# AuxPowerSupply.net
KiCad netlist of a schematic drawn in Altium Designer
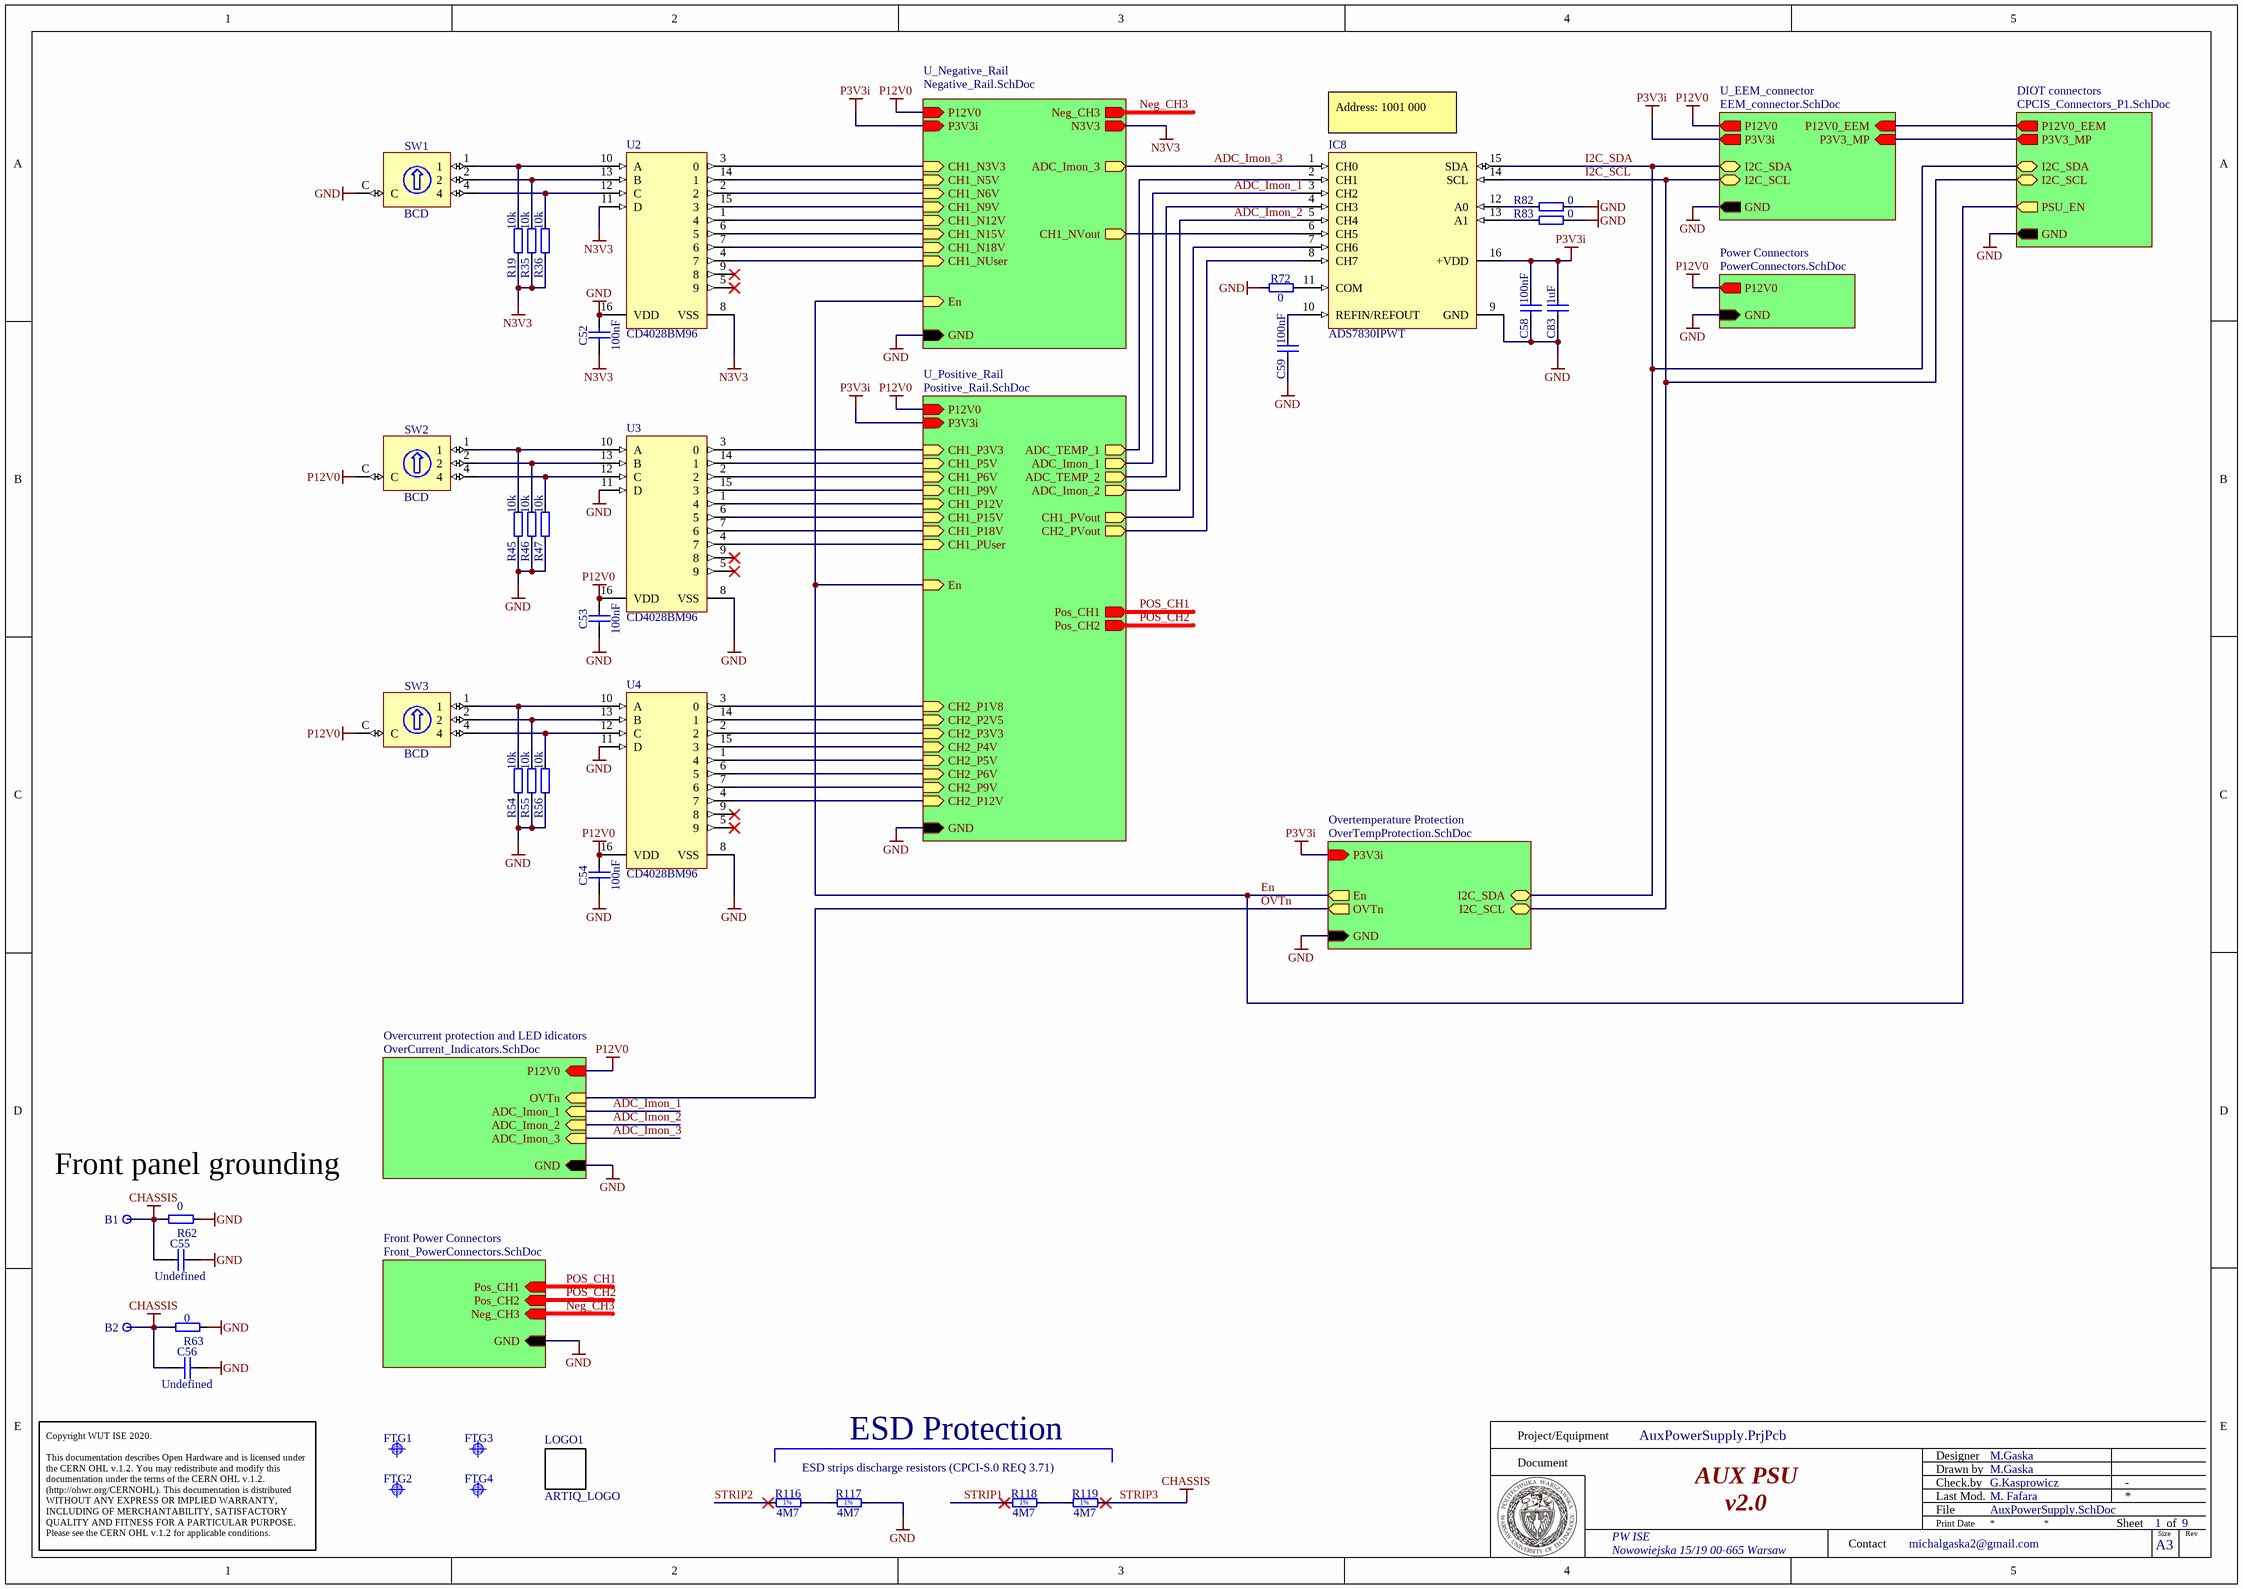
[diagram p0: AuxPowerSupply.SchDoc]

(export (version "E")
  (design (tool "Eeschema 10.0.6"))
  (components
    (comp (ref "B1")
      (value "~")
      (footprint "MTG270_500")
      (description "Single Terminal Socket")
      (fields (field (name "PART NUMBER") "PLATED_HOLE2.7_PAD5.0") (field (name "AUTHOR") "CERN DEM JMW"))
      (libsource (lib "Eletro-mechanical") (part "Single Terminal Socket"))
    )
    (comp (ref "B2")
      (value "~")
      (footprint "MTG270_500")
      (description "Single Terminal Socket")
      (fields (field (name "PART NUMBER") "PLATED_HOLE2.7_PAD5.0") (field (name "AUTHOR") "CERN DEM JMW"))
      (libsource (lib "Eletro-mechanical") (part "Single Terminal Socket"))
    )
    (comp (ref "C52")
      (value "100nF")
      (footprint "CAPC1608X87N")
      (description "Non-polarised capacitor")
      (fields
        (field (name "PART NUMBER") "CC0603_100NF_50V_10%_X5R")
        (field (name "VOLTAGE") "50V")
        (field (name "AUTHOR") "CERN DEM MR")
      )
      (libsource (lib "Capacitors") (part "Capacitor - non polarized"))
    )
    (comp (ref "C53")
      (value "100nF")
      (footprint "CAPC1608X87N")
      (description "Non-polarised capacitor")
      (fields
        (field (name "PART NUMBER") "CC0603_100NF_50V_10%_X5R")
        (field (name "VOLTAGE") "50V")
        (field (name "AUTHOR") "CERN DEM MR")
      )
      (libsource (lib "Capacitors") (part "Capacitor - non polarized"))
    )
    (comp (ref "C54")
      (value "100nF")
      (footprint "CAPC1608X87N")
      (description "Non-polarised capacitor")
      (fields
        (field (name "PART NUMBER") "CC0603_100NF_50V_10%_X5R")
        (field (name "VOLTAGE") "50V")
        (field (name "AUTHOR") "CERN DEM MR")
      )
      (libsource (lib "Capacitors") (part "Capacitor - non polarized"))
    )
    (comp (ref "C55")
      (value "Undefined")
      (footprint "CAPC2012X135N")
      (description "Non-polarised capacitor")
      (fields (field (name "PART NUMBER") "CC0805_NO-VALUE") (field (name "AUTHOR") "CERN DEM JLC"))
      (libsource (lib "Capacitors") (part "Capacitor - non polarized"))
    )
    (comp (ref "C56")
      (value "Undefined")
      (footprint "CAPC2012X135N")
      (description "Non-polarised capacitor")
      (fields (field (name "PART NUMBER") "CC0805_NO-VALUE") (field (name "AUTHOR") "CERN DEM JLC"))
      (libsource (lib "Capacitors") (part "Capacitor - non polarized"))
    )
    (comp (ref "C58")
      (value "100nF")
      (footprint "CAPC1608X87N")
      (description "Non-polarised capacitor")
      (fields
        (field (name "PART NUMBER") "CC0603_100NF_50V_10%_X5R")
        (field (name "VOLTAGE") "50V")
        (field (name "AUTHOR") "CERN DEM MR")
      )
      (libsource (lib "Capacitors") (part "Capacitor - non polarized"))
    )
    (comp (ref "C59")
      (value "100nF")
      (footprint "CAPC1608X87N")
      (description "Non-polarised capacitor")
      (fields
        (field (name "PART NUMBER") "CC0603_100NF_50V_10%_X5R")
        (field (name "VOLTAGE") "50V")
        (field (name "AUTHOR") "CERN DEM MR")
      )
      (libsource (lib "Capacitors") (part "Capacitor - non polarized"))
    )
    (comp (ref "C83")
      (value "1uF")
      (footprint "CAPC1608X87N")
      (description "Non-polarised capacitor")
      (fields
        (field (name "PART NUMBER") "CC0603_1UF_25V_10%_X7R")
        (field (name "VOLTAGE") "25V")
        (field (name "AUTHOR") "CERN DEM JLC")
      )
      (libsource (lib "Capacitors") (part "Capacitor - non polarized"))
    )
    (comp (ref "FTG1")
      (value "~")
      (footprint "FIDUCIAL_TOP_C100-200")
      (description "Fiducial Target")
      (fields (field (name "PART NUMBER") "FIDUCIAL_TARGET_C100-200") (field (name "AUTHOR") "CERN DEM JLC"))
      (libsource (lib "Eletro-mechanical") (part "Fiducial Target"))
    )
    (comp (ref "FTG2")
      (value "~")
      (footprint "FIDUCIAL_TOP_S100-200")
      (description "Fiducial Target")
      (fields (field (name "PART NUMBER") "FIDUCIAL_TARGET_S100-200") (field (name "AUTHOR") "CERN DEM JLC"))
      (libsource (lib "Eletro-mechanical") (part "Fiducial Target"))
    )
    (comp (ref "FTG3")
      (value "~")
      (footprint "FIDUCIAL_TOP_S100-200")
      (description "Fiducial Target")
      (fields (field (name "PART NUMBER") "FIDUCIAL_TARGET_S100-200") (field (name "AUTHOR") "CERN DEM JLC"))
      (libsource (lib "Eletro-mechanical") (part "Fiducial Target"))
    )
    (comp (ref "FTG4")
      (value "~")
      (footprint "FIDUCIAL_TOP_S100-200")
      (description "Fiducial Target")
      (fields (field (name "PART NUMBER") "FIDUCIAL_TARGET_S100-200") (field (name "AUTHOR") "CERN DEM JLC"))
      (libsource (lib "Eletro-mechanical") (part "Fiducial Target"))
    )
    (comp (ref "IC8")
      (value "ADS7830IPWT")
      (footprint "SOP65P640X120-16N")
      (description "8-Bit, 8-Channel Sampling A/D Converter with I2C Interface 16-TSSOP -40 to 85")
      (fields (field (name "MF") "Texas Instruments"))
      (libsource (lib "MG_lib") (part "ADS7830IPWT"))
    )
    (comp (ref "LOGO1")
      (value "ARTIQ_LOGO")
      (footprint "ARTIQ_Logo")
      (description "ARTIQ logo to place on the PCB")
      (libsource (lib "TechnoSystem Workspace") (part "ARTIQ_Logo"))
    )
    (comp (ref "R19")
      (value "10k")
      (footprint "RESC1608X55N")
      (description "Resistor - 1%")
      (fields
        (field (name "PART NUMBER") "R0603_10K_1%_0.1W_100PPM")
        (field (name "POWER") "0.1W")
        (field (name "AUTHOR") "CERN DEM JLC")
      )
      (libsource (lib "Resistors") (part "Resistor - 1%"))
    )
    (comp (ref "R35")
      (value "10k")
      (footprint "RESC1608X55N")
      (description "Resistor - 1%")
      (fields
        (field (name "PART NUMBER") "R0603_10K_1%_0.1W_100PPM")
        (field (name "POWER") "0.1W")
        (field (name "AUTHOR") "CERN DEM JLC")
      )
      (libsource (lib "Resistors") (part "Resistor - 1%"))
    )
    (comp (ref "R36")
      (value "10k")
      (footprint "RESC1608X55N")
      (description "Resistor - 1%")
      (fields
        (field (name "PART NUMBER") "R0603_10K_1%_0.1W_100PPM")
        (field (name "POWER") "0.1W")
        (field (name "AUTHOR") "CERN DEM JLC")
      )
      (libsource (lib "Resistors") (part "Resistor - 1%"))
    )
    (comp (ref "R45")
      (value "10k")
      (footprint "RESC1608X55N")
      (description "Resistor - 1%")
      (fields
        (field (name "PART NUMBER") "R0603_10K_1%_0.1W_100PPM")
        (field (name "POWER") "0.1W")
        (field (name "AUTHOR") "CERN DEM JLC")
      )
      (libsource (lib "Resistors") (part "Resistor - 1%"))
    )
    (comp (ref "R46")
      (value "10k")
      (footprint "RESC1608X55N")
      (description "Resistor - 1%")
      (fields
        (field (name "PART NUMBER") "R0603_10K_1%_0.1W_100PPM")
        (field (name "POWER") "0.1W")
        (field (name "AUTHOR") "CERN DEM JLC")
      )
      (libsource (lib "Resistors") (part "Resistor - 1%"))
    )
    (comp (ref "R47")
      (value "10k")
      (footprint "RESC1608X55N")
      (description "Resistor - 1%")
      (fields
        (field (name "PART NUMBER") "R0603_10K_1%_0.1W_100PPM")
        (field (name "POWER") "0.1W")
        (field (name "AUTHOR") "CERN DEM JLC")
      )
      (libsource (lib "Resistors") (part "Resistor - 1%"))
    )
    (comp (ref "R54")
      (value "10k")
      (footprint "RESC1608X55N")
      (description "Resistor - 1%")
      (fields
        (field (name "PART NUMBER") "R0603_10K_1%_0.1W_100PPM")
        (field (name "POWER") "0.1W")
        (field (name "AUTHOR") "CERN DEM JLC")
      )
      (libsource (lib "Resistors") (part "Resistor - 1%"))
    )
    (comp (ref "R55")
      (value "10k")
      (footprint "RESC1608X55N")
      (description "Resistor - 1%")
      (fields
        (field (name "PART NUMBER") "R0603_10K_1%_0.1W_100PPM")
        (field (name "POWER") "0.1W")
        (field (name "AUTHOR") "CERN DEM JLC")
      )
      (libsource (lib "Resistors") (part "Resistor - 1%"))
    )
    (comp (ref "R56")
      (value "10k")
      (footprint "RESC1608X55N")
      (description "Resistor - 1%")
      (fields
        (field (name "PART NUMBER") "R0603_10K_1%_0.1W_100PPM")
        (field (name "POWER") "0.1W")
        (field (name "AUTHOR") "CERN DEM JLC")
      )
      (libsource (lib "Resistors") (part "Resistor - 1%"))
    )
    (comp (ref "R62")
      (value "0")
      (footprint "RESC1608X55N")
      (description "Resistor")
      (fields
        (field (name "PART NUMBER") "R0603_0R_JUMPER")
        (field (name "MANUFACTURER") "GENERIC")
        (field (name "AUTHOR") "CERN DEM JLC")
      )
      (libsource (lib "Resistors") (part "Resistor"))
    )
    (comp (ref "R63")
      (value "0")
      (footprint "RESC1608X55N")
      (description "Resistor")
      (fields
        (field (name "PART NUMBER") "R0603_0R_JUMPER")
        (field (name "MANUFACTURER") "GENERIC")
        (field (name "AUTHOR") "CERN DEM JLC")
      )
      (libsource (lib "Resistors") (part "Resistor"))
    )
    (comp (ref "R72")
      (value "0")
      (footprint "RESC1608X55N")
      (description "Resistor")
      (fields
        (field (name "PART NUMBER") "R0603_0R_JUMPER")
        (field (name "MANUFACTURER") "GENERIC")
        (field (name "AUTHOR") "CERN DEM JLC")
      )
      (libsource (lib "Resistors") (part "Resistor"))
    )
    (comp (ref "R82")
      (value "0")
      (footprint "RESC1608X55N")
      (description "Resistor")
      (fields
        (field (name "PART NUMBER") "R0603_0R_JUMPER")
        (field (name "MANUFACTURER") "GENERIC")
        (field (name "AUTHOR") "CERN DEM JLC")
      )
      (libsource (lib "Resistors") (part "Resistor"))
    )
    (comp (ref "R83")
      (value "0")
      (footprint "RESC1608X55N")
      (description "Resistor")
      (fields
        (field (name "PART NUMBER") "R0603_0R_JUMPER")
        (field (name "MANUFACTURER") "GENERIC")
        (field (name "AUTHOR") "CERN DEM JLC")
      )
      (libsource (lib "Resistors") (part "Resistor"))
    )
    (comp (ref "R116")
      (value "4M7")
      (footprint "RESC2113X55N")
      (description "Resistor - 1%")
      (fields
        (field (name "PART NUMBER") "R0805_4M7_1%_0.125W_100PPM_VISHAY_CRCW e3")
        (field (name "POWER") "0.125W")
        (field (name "AUTHOR") "CERN DEM BR")
      )
      (libsource (lib "") (part "Resistor - 1%_1"))
    )
    (comp (ref "R117")
      (value "4M7")
      (footprint "RESC2113X55N")
      (description "Resistor - 1%")
      (fields
        (field (name "PART NUMBER") "R0805_4M7_1%_0.125W_100PPM_VISHAY_CRCW e3")
        (field (name "POWER") "0.125W")
        (field (name "AUTHOR") "CERN DEM BR")
      )
      (libsource (lib "") (part "Resistor - 1%_1"))
    )
    (comp (ref "R118")
      (value "4M7")
      (footprint "RESC2113X55N")
      (description "Resistor - 1%")
      (fields
        (field (name "PART NUMBER") "R0805_4M7_1%_0.125W_100PPM_VISHAY_CRCW e3")
        (field (name "POWER") "0.125W")
        (field (name "AUTHOR") "CERN DEM BR")
      )
      (libsource (lib "") (part "Resistor - 1%_1"))
    )
    (comp (ref "R119")
      (value "4M7")
      (footprint "RESC2113X55N")
      (description "Resistor - 1%")
      (fields
        (field (name "PART NUMBER") "R0805_4M7_1%_0.125W_100PPM_VISHAY_CRCW e3")
        (field (name "POWER") "0.125W")
        (field (name "AUTHOR") "CERN DEM BR")
      )
      (libsource (lib "") (part "Resistor - 1%_1"))
    )
    (comp (ref "SW1")
      (value "BCD")
      (footprint "SW_NIDEC-COPAL-ELECTRONICS_S-81X1")
      (description "Rotary Code Switch 1 2 4 C")
      (fields
        (field (name "PART NUMBER") "SW_NIDEC-COPAL-ELECTRONICS_S-8111")
        (field (name "MANUFACTURER") "NIDEC-COPAL-ELECTRONICS")
        (field (name "AUTHOR") "CERN DEM BC")
      )
      (libsource (lib "Switches_Relays") (part "SW_Rotary_S-8111"))
    )
    (comp (ref "SW2")
      (value "BCD")
      (footprint "SW_NIDEC-COPAL-ELECTRONICS_S-81X1")
      (description "Rotary Code Switch 1 2 4 C")
      (fields
        (field (name "PART NUMBER") "SW_NIDEC-COPAL-ELECTRONICS_S-8111")
        (field (name "MANUFACTURER") "NIDEC-COPAL-ELECTRONICS")
        (field (name "AUTHOR") "CERN DEM BC")
      )
      (libsource (lib "Switches_Relays") (part "SW_Rotary_S-8111"))
    )
    (comp (ref "SW3")
      (value "BCD")
      (footprint "SW_NIDEC-COPAL-ELECTRONICS_S-81X1")
      (description "Rotary Code Switch 1 2 4 C")
      (fields
        (field (name "PART NUMBER") "SW_NIDEC-COPAL-ELECTRONICS_S-8111")
        (field (name "MANUFACTURER") "NIDEC-COPAL-ELECTRONICS")
        (field (name "AUTHOR") "CERN DEM BC")
      )
      (libsource (lib "Switches_Relays") (part "SW_Rotary_S-8111"))
    )
    (comp (ref "U2")
      (value "CD4028BM96")
      (footprint "D0016A_M")
      (description "Decimal Decoder/Driver, 4000/14000/40000 Series, True Output, CMOS, PDSO16")
      (libsource (lib "TechnoSystem Workspace") (part "TI-CD4028B-16"))
    )
    (comp (ref "U3")
      (value "CD4028BM96")
      (footprint "D0016A_M")
      (description "Decimal Decoder/Driver, 4000/14000/40000 Series, True Output, CMOS, PDSO16")
      (libsource (lib "TechnoSystem Workspace") (part "TI-CD4028B-16"))
    )
    (comp (ref "U4")
      (value "CD4028BM96")
      (footprint "D0016A_M")
      (description "Decimal Decoder/Driver, 4000/14000/40000 Series, True Output, CMOS, PDSO16")
      (libsource (lib "TechnoSystem Workspace") (part "TI-CD4028B-16"))
    )
  )
  (nets
    (net (code "1") (name "/ADC_Imon_1") (class "Default")
      (node (ref "IC8") (pin "3") (pinfunction "CH2_3") (pintype "input"))
    )
    (net (code "2") (name "/ADC_Imon_2") (class "Default")
      (node (ref "IC8") (pin "5") (pinfunction "CH4_5") (pintype "input"))
    )
    (net (code "3") (name "/ADC_Imon_3") (class "Default")
      (node (ref "IC8") (pin "1") (pinfunction "CH0_1") (pintype "input"))
    )
    (net (code "4") (name "/ADC_TEMP_1") (class "Default")
      (node (ref "IC8") (pin "2") (pinfunction "CH1_2") (pintype "input"))
    )
    (net (code "5") (name "/ADC_TEMP_2") (class "Default")
      (node (ref "IC8") (pin "4") (pinfunction "CH3_4") (pintype "input"))
    )
    (net (code "6") (name "/CH1_N3V3") (class "Default")
      (node (ref "U2") (pin "3") (pinfunction "0_3") (pintype "output"))
    )
    (net (code "7") (name "/CH1_N5V") (class "Default")
      (node (ref "U2") (pin "14") (pinfunction "1_14") (pintype "output"))
    )
    (net (code "8") (name "/CH1_N6V") (class "Default")
      (node (ref "U2") (pin "2") (pinfunction "2_2") (pintype "output"))
    )
    (net (code "9") (name "/CH1_N9V") (class "Default")
      (node (ref "U2") (pin "15") (pinfunction "3_15") (pintype "output"))
    )
    (net (code "10") (name "/CH1_N12V") (class "Default")
      (node (ref "U2") (pin "1") (pinfunction "4_1") (pintype "output"))
    )
    (net (code "11") (name "/CH1_N15V") (class "Default")
      (node (ref "U2") (pin "6") (pinfunction "5_6") (pintype "output"))
    )
    (net (code "12") (name "/CH1_N18V") (class "Default")
      (node (ref "U2") (pin "7") (pinfunction "6_7") (pintype "output"))
    )
    (net (code "13") (name "/CH1_NUser") (class "Default")
      (node (ref "U2") (pin "4") (pinfunction "7_4") (pintype "output"))
    )
    (net (code "14") (name "/CH1_NVout") (class "Default")
      (node (ref "IC8") (pin "6") (pinfunction "CH5_6") (pintype "input"))
    )
    (net (code "15") (name "/CH1_P3V3") (class "Default")
      (node (ref "U3") (pin "3") (pinfunction "0_3") (pintype "output"))
    )
    (net (code "16") (name "/CH1_P5V") (class "Default")
      (node (ref "U3") (pin "14") (pinfunction "1_14") (pintype "output"))
    )
    (net (code "17") (name "/CH1_P6V") (class "Default")
      (node (ref "U3") (pin "2") (pinfunction "2_2") (pintype "output"))
    )
    (net (code "18") (name "/CH1_P9V") (class "Default")
      (node (ref "U3") (pin "15") (pinfunction "3_15") (pintype "output"))
    )
    (net (code "19") (name "/CH1_P12V") (class "Default")
      (node (ref "U3") (pin "1") (pinfunction "4_1") (pintype "output"))
    )
    (net (code "20") (name "/CH1_P15V") (class "Default")
      (node (ref "U3") (pin "6") (pinfunction "5_6") (pintype "output"))
    )
    (net (code "21") (name "/CH1_P18V") (class "Default")
      (node (ref "U3") (pin "7") (pinfunction "6_7") (pintype "output"))
    )
    (net (code "22") (name "/CH1_PUser") (class "Default")
      (node (ref "U3") (pin "4") (pinfunction "7_4") (pintype "output"))
    )
    (net (code "23") (name "/CH1_PVout") (class "Default")
      (node (ref "IC8") (pin "7") (pinfunction "CH6_7") (pintype "input"))
    )
    (net (code "24") (name "/CH2_P1V8") (class "Default")
      (node (ref "U4") (pin "3") (pinfunction "0_3") (pintype "output"))
    )
    (net (code "25") (name "/CH2_P2V5") (class "Default")
      (node (ref "U4") (pin "14") (pinfunction "1_14") (pintype "output"))
    )
    (net (code "26") (name "/CH2_P3V3") (class "Default")
      (node (ref "U4") (pin "2") (pinfunction "2_2") (pintype "output"))
    )
    (net (code "27") (name "/CH2_P4V") (class "Default")
      (node (ref "U4") (pin "15") (pinfunction "3_15") (pintype "output"))
    )
    (net (code "28") (name "/CH2_P5V") (class "Default")
      (node (ref "U4") (pin "1") (pinfunction "4_1") (pintype "output"))
    )
    (net (code "29") (name "/CH2_P6V") (class "Default")
      (node (ref "U4") (pin "6") (pinfunction "5_6") (pintype "output"))
    )
    (net (code "30") (name "/CH2_P9V") (class "Default")
      (node (ref "U4") (pin "7") (pinfunction "6_7") (pintype "output"))
    )
    (net (code "31") (name "/CH2_P12V") (class "Default")
      (node (ref "U4") (pin "4") (pinfunction "7_4") (pintype "output"))
    )
    (net (code "32") (name "/CH2_PVout") (class "Default")
      (node (ref "IC8") (pin "8") (pinfunction "CH7_8") (pintype "input"))
    )
    (net (code "34") (name "/I2C_SCL") (class "Default")
      (node (ref "IC8") (pin "14") (pinfunction "SCL_14") (pintype "input"))
    )
    (net (code "35") (name "/I2C_SDA") (class "Default")
      (node (ref "IC8") (pin "15") (pinfunction "SDA_15") (pintype "bidirectional"))
    )
    (net (code "42") (name "/STRIP1") (class "Default")
      (node (ref "R118") (pin "1") (pinfunction "1_1") (pintype "passive+no_connect"))
    )
    (net (code "43") (name "/STRIP2") (class "Default")
      (node (ref "R116") (pin "1") (pinfunction "1_1") (pintype "passive+no_connect"))
    )
    (net (code "44") (name "CHASSIS") (class "Default")
      (node (ref "B1") (pin "1") (pinfunction "1_1") (pintype "bidirectional"))
      (node (ref "B2") (pin "1") (pinfunction "1_1") (pintype "bidirectional"))
      (node (ref "C55") (pin "1") (pinfunction "1_1") (pintype "passive"))
      (node (ref "C56") (pin "1") (pinfunction "1_1") (pintype "passive"))
      (node (ref "R119") (pin "2") (pinfunction "2_2") (pintype "passive"))
      (node (ref "R62") (pin "2") (pinfunction "2_2") (pintype "passive"))
      (node (ref "R63") (pin "2") (pinfunction "2_2") (pintype "passive"))
    )
    (net (code "45") (name "GND") (class "Default")
      (node (ref "C52") (pin "2") (pinfunction "2_2") (pintype "passive"))
      (node (ref "C53") (pin "1") (pinfunction "1_1") (pintype "passive"))
      (node (ref "C54") (pin "1") (pinfunction "1_1") (pintype "passive"))
      (node (ref "C55") (pin "2") (pinfunction "2_2") (pintype "passive"))
      (node (ref "C56") (pin "2") (pinfunction "2_2") (pintype "passive"))
      (node (ref "C58") (pin "1") (pinfunction "1_1") (pintype "passive"))
      (node (ref "C59") (pin "1") (pinfunction "1_1") (pintype "passive"))
      (node (ref "C83") (pin "1") (pinfunction "1_1") (pintype "passive"))
      (node (ref "IC8") (pin "9") (pinfunction "GND_9") (pintype "power_in"))
      (node (ref "R117") (pin "2") (pinfunction "2_2") (pintype "passive"))
      (node (ref "R45") (pin "1") (pinfunction "1_1") (pintype "passive"))
      (node (ref "R46") (pin "1") (pinfunction "1_1") (pintype "passive"))
      (node (ref "R47") (pin "1") (pinfunction "1_1") (pintype "passive"))
      (node (ref "R54") (pin "1") (pinfunction "1_1") (pintype "passive"))
      (node (ref "R55") (pin "1") (pinfunction "1_1") (pintype "passive"))
      (node (ref "R56") (pin "1") (pinfunction "1_1") (pintype "passive"))
      (node (ref "R62") (pin "1") (pinfunction "1_1") (pintype "passive"))
      (node (ref "R63") (pin "1") (pinfunction "1_1") (pintype "passive"))
      (node (ref "R72") (pin "1") (pinfunction "1_1") (pintype "passive"))
      (node (ref "R82") (pin "2") (pinfunction "2_2") (pintype "passive"))
      (node (ref "R83") (pin "2") (pinfunction "2_2") (pintype "passive"))
      (node (ref "SW1") (pin "C") (pinfunction "C_C") (pintype "bidirectional"))
      (node (ref "U2") (pin "16") (pinfunction "VDD_16") (pintype "power_in"))
      (node (ref "U3") (pin "11") (pinfunction "D_11") (pintype "input"))
      (node (ref "U3") (pin "8") (pinfunction "VSS_8") (pintype "power_in"))
      (node (ref "U4") (pin "11") (pinfunction "D_11") (pintype "input"))
      (node (ref "U4") (pin "8") (pinfunction "VSS_8") (pintype "power_in"))
    )
    (net (code "46") (name "N3V3") (class "Default")
      (node (ref "C52") (pin "1") (pinfunction "1_1") (pintype "passive"))
      (node (ref "R19") (pin "1") (pinfunction "1_1") (pintype "passive"))
      (node (ref "R35") (pin "1") (pinfunction "1_1") (pintype "passive"))
      (node (ref "R36") (pin "1") (pinfunction "1_1") (pintype "passive"))
      (node (ref "U2") (pin "11") (pinfunction "D_11") (pintype "input"))
      (node (ref "U2") (pin "8") (pinfunction "VSS_8") (pintype "power_in"))
    )
    (net (code "47") (name "Net-(IC8-A0)") (class "Default")
      (node (ref "IC8") (pin "12") (pinfunction "A0_12") (pintype "input"))
      (node (ref "R82") (pin "1") (pinfunction "1_1") (pintype "passive"))
    )
    (net (code "48") (name "Net-(IC8-A1)") (class "Default")
      (node (ref "IC8") (pin "13") (pinfunction "A1_13") (pintype "input"))
      (node (ref "R83") (pin "1") (pinfunction "1_1") (pintype "passive"))
    )
    (net (code "49") (name "Net-(IC8-COM)") (class "Default")
      (node (ref "IC8") (pin "11") (pinfunction "COM_11") (pintype "input"))
      (node (ref "R72") (pin "2") (pinfunction "2_2") (pintype "passive"))
    )
    (net (code "50") (name "Net-(IC8-REFIN{slash}REFOUT)") (class "Default")
      (node (ref "C59") (pin "2") (pinfunction "2_2") (pintype "passive"))
      (node (ref "IC8") (pin "10") (pinfunction "REFIN/REFOUT_10") (pintype "input"))
    )
    (net (code "51") (name "Net-(R116-Pad2)") (class "Default")
      (node (ref "R116") (pin "2") (pinfunction "2_2") (pintype "passive"))
      (node (ref "R117") (pin "1") (pinfunction "1_1") (pintype "passive"))
    )
    (net (code "52") (name "Net-(R118-Pad2)") (class "Default")
      (node (ref "R118") (pin "2") (pinfunction "2_2") (pintype "passive"))
      (node (ref "R119") (pin "1") (pinfunction "1_1") (pintype "passive"))
    )
    (net (code "53") (name "Net-(U2-A)") (class "Default")
      (node (ref "R19") (pin "2") (pinfunction "2_2") (pintype "passive"))
      (node (ref "SW1") (pin "1") (pinfunction "1_1") (pintype "bidirectional"))
      (node (ref "U2") (pin "10") (pinfunction "A_10") (pintype "input"))
    )
    (net (code "54") (name "Net-(U2-B)") (class "Default")
      (node (ref "R35") (pin "2") (pinfunction "2_2") (pintype "passive"))
      (node (ref "SW1") (pin "2") (pinfunction "2_2") (pintype "bidirectional"))
      (node (ref "U2") (pin "13") (pinfunction "B_13") (pintype "input"))
    )
    (net (code "55") (name "Net-(U2-C)") (class "Default")
      (node (ref "R36") (pin "2") (pinfunction "2_2") (pintype "passive"))
      (node (ref "SW1") (pin "4") (pinfunction "4_4") (pintype "bidirectional"))
      (node (ref "U2") (pin "12") (pinfunction "C_12") (pintype "input"))
    )
    (net (code "56") (name "Net-(U3-A)") (class "Default")
      (node (ref "R45") (pin "2") (pinfunction "2_2") (pintype "passive"))
      (node (ref "SW2") (pin "1") (pinfunction "1_1") (pintype "bidirectional"))
      (node (ref "U3") (pin "10") (pinfunction "A_10") (pintype "input"))
    )
    (net (code "57") (name "Net-(U3-B)") (class "Default")
      (node (ref "R46") (pin "2") (pinfunction "2_2") (pintype "passive"))
      (node (ref "SW2") (pin "2") (pinfunction "2_2") (pintype "bidirectional"))
      (node (ref "U3") (pin "13") (pinfunction "B_13") (pintype "input"))
    )
    (net (code "58") (name "Net-(U3-C)") (class "Default")
      (node (ref "R47") (pin "2") (pinfunction "2_2") (pintype "passive"))
      (node (ref "SW2") (pin "4") (pinfunction "4_4") (pintype "bidirectional"))
      (node (ref "U3") (pin "12") (pinfunction "C_12") (pintype "input"))
    )
    (net (code "59") (name "Net-(U4-A)") (class "Default")
      (node (ref "R54") (pin "2") (pinfunction "2_2") (pintype "passive"))
      (node (ref "SW3") (pin "1") (pinfunction "1_1") (pintype "bidirectional"))
      (node (ref "U4") (pin "10") (pinfunction "A_10") (pintype "input"))
    )
    (net (code "60") (name "Net-(U4-B)") (class "Default")
      (node (ref "R55") (pin "2") (pinfunction "2_2") (pintype "passive"))
      (node (ref "SW3") (pin "2") (pinfunction "2_2") (pintype "bidirectional"))
      (node (ref "U4") (pin "13") (pinfunction "B_13") (pintype "input"))
    )
    (net (code "61") (name "Net-(U4-C)") (class "Default")
      (node (ref "R56") (pin "2") (pinfunction "2_2") (pintype "passive"))
      (node (ref "SW3") (pin "4") (pinfunction "4_4") (pintype "bidirectional"))
      (node (ref "U4") (pin "12") (pinfunction "C_12") (pintype "input"))
    )
    (net (code "62") (name "P3V3i") (class "Default")
      (node (ref "C58") (pin "2") (pinfunction "2_2") (pintype "passive"))
      (node (ref "C83") (pin "2") (pinfunction "2_2") (pintype "passive"))
      (node (ref "IC8") (pin "16") (pinfunction "+VDD_16") (pintype "power_in"))
    )
    (net (code "63") (name "P12V0") (class "Default")
      (node (ref "C53") (pin "2") (pinfunction "2_2") (pintype "passive"))
      (node (ref "C54") (pin "2") (pinfunction "2_2") (pintype "passive"))
      (node (ref "SW2") (pin "C") (pinfunction "C_C") (pintype "bidirectional"))
      (node (ref "SW3") (pin "C") (pinfunction "C_C") (pintype "bidirectional"))
      (node (ref "U3") (pin "16") (pinfunction "VDD_16") (pintype "power_in"))
      (node (ref "U4") (pin "16") (pinfunction "VDD_16") (pintype "power_in"))
    )
    (net (code "64") (name "unconnected-(U2-8-Pad9)") (class "Default")
      (node (ref "U2") (pin "9") (pinfunction "8_9") (pintype "output+no_connect"))
    )
    (net (code "65") (name "unconnected-(U2-9-Pad5)") (class "Default")
      (node (ref "U2") (pin "5") (pinfunction "9_5") (pintype "output+no_connect"))
    )
    (net (code "66") (name "unconnected-(U3-8-Pad9)") (class "Default")
      (node (ref "U3") (pin "9") (pinfunction "8_9") (pintype "output+no_connect"))
    )
    (net (code "67") (name "unconnected-(U3-9-Pad5)") (class "Default")
      (node (ref "U3") (pin "5") (pinfunction "9_5") (pintype "output+no_connect"))
    )
    (net (code "68") (name "unconnected-(U4-8-Pad9)") (class "Default")
      (node (ref "U4") (pin "9") (pinfunction "8_9") (pintype "output+no_connect"))
    )
    (net (code "69") (name "unconnected-(U4-9-Pad5)") (class "Default")
      (node (ref "U4") (pin "5") (pinfunction "9_5") (pintype "output+no_connect"))
    )
  )
)
